# OMD_DRIVER_60V.net
KiCad netlist of a schematic drawn in Altium Designer
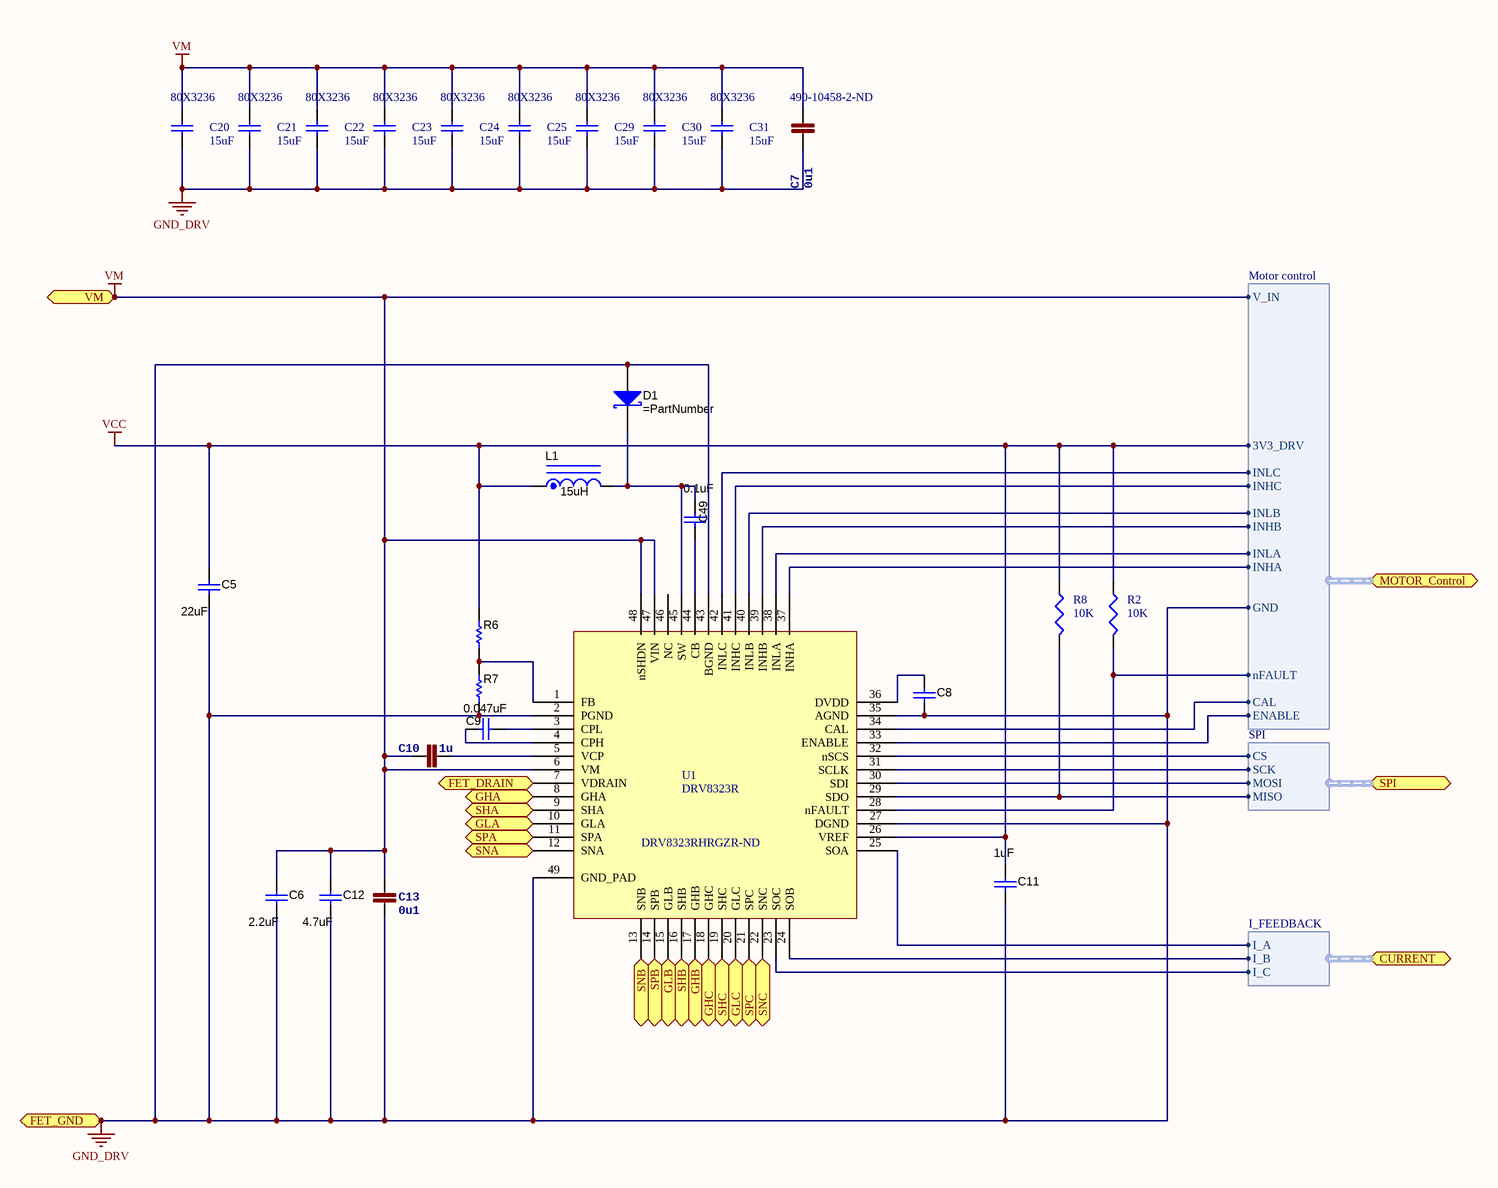
[diagram p0: OMD_DRIVER_60V.SchDoc]

(export (version "E")
  (design (tool "Eeschema 10.0.6"))
  (components
    (comp (ref "C5")
      (value "22uF")
      (footprint "1206_180L")
      (description "CAP, CERM, 22 µF, 10 V, +/- 20%, X7S, 1206")
      (libsource (lib "OMD") (part "C3216X7S1A226M160AC"))
    )
    (comp (ref "C6")
      (value "2.2uF")
      (footprint "1210L")
      (description "CAP, CERM, 2.2 µF, 100 V, +/- 10%, X7R, 1210")
      (libsource (lib "OMD") (part "HMK325B7225KN-T"))
    )
    (comp (ref "C7")
      (value "0u1")
      (footprint "0402-CAP")
      (description "CAP CER 0.1UF 16V Y5V 0402")
      (fields (field (name "SUPPLIER PART NUMBER 1") "490-10458-2-ND"))
      (libsource (lib "OMD") (part "CAP0402"))
    )
    (comp (ref "C8")
      (value "~")
      (footprint "0603-CAP")
      (description "CAP, CERM, 1 µF, 6.3 V, +/- 10%, X7R, 0603")
      (libsource (lib "OMD") (part "GRM188R70J105KA01D"))
    )
    (comp (ref "C9")
      (value "0.047uF")
      (footprint "0603-CAP")
      (description "CAP, CERM, 0.047 µF, 100 V, +/- 10%, X7S, 0603")
      (libsource (lib "OMD") (part "C1608X7S2A473K080AB"))
    )
    (comp (ref "C10")
      (value "1u")
      (footprint "0805-CAP")
      (description "CAP CER 1UF 16V Y5V 0603")
      (libsource (lib "OMD") (part "CAP0603"))
    )
    (comp (ref "C11")
      (value "1uF")
      (footprint "0603-CAP")
      (description "CAP, CERM, 1 µF, 6.3 V, +/- 10%, X7R, 0603")
      (libsource (lib "OMD") (part "GRM188R70J105KA01D"))
    )
    (comp (ref "C12")
      (value "4.7uF")
      (footprint "1210_270L")
      (description "CAP, CERM, 4.7 µF, 80 V, +/- 10%, X7R, 1210")
      (libsource (lib "OMD") (part "GRM32ER71K475KE14L"))
    )
    (comp (ref "C13")
      (value "0u1")
      (footprint "0402-CAP")
      (description "CAP CER 0.1UF 16V Y5V 0402")
      (libsource (lib "OMD") (part "CAP0402"))
    )
    (comp (ref "C20")
      (value "15uF")
      (footprint "CAPC5750L")
      (description "Capacitor")
      (fields (field (name "SUPPLIER PART NUMBER 1") "80X3236") (field (name "Comment") "Cap"))
      (libsource (lib "OMD") (part "Cap"))
    )
    (comp (ref "C21")
      (value "15uF")
      (footprint "CAPC5750L")
      (description "Capacitor")
      (fields (field (name "SUPPLIER PART NUMBER 1") "80X3236") (field (name "Comment") "Cap"))
      (libsource (lib "OMD") (part "Cap"))
    )
    (comp (ref "C22")
      (value "15uF")
      (footprint "CAPC5750L")
      (description "Capacitor")
      (fields (field (name "SUPPLIER PART NUMBER 1") "80X3236") (field (name "Comment") "Cap"))
      (libsource (lib "OMD") (part "Cap"))
    )
    (comp (ref "C23")
      (value "15uF")
      (footprint "CAPC5750L")
      (description "Capacitor")
      (fields (field (name "SUPPLIER PART NUMBER 1") "80X3236") (field (name "Comment") "Cap"))
      (libsource (lib "OMD") (part "Cap"))
    )
    (comp (ref "C24")
      (value "15uF")
      (footprint "CAPC5750L")
      (description "Capacitor")
      (fields (field (name "SUPPLIER PART NUMBER 1") "80X3236") (field (name "Comment") "Cap"))
      (libsource (lib "OMD") (part "Cap"))
    )
    (comp (ref "C25")
      (value "15uF")
      (footprint "CAPC5750L")
      (description "Capacitor")
      (fields (field (name "SUPPLIER PART NUMBER 1") "80X3236") (field (name "Comment") "Cap"))
      (libsource (lib "OMD") (part "Cap"))
    )
    (comp (ref "C29")
      (value "15uF")
      (footprint "CAPC5750L")
      (description "Capacitor")
      (fields (field (name "SUPPLIER PART NUMBER 1") "80X3236") (field (name "Comment") "Cap"))
      (libsource (lib "OMD") (part "Cap"))
    )
    (comp (ref "C30")
      (value "15uF")
      (footprint "CAPC5750L")
      (description "Capacitor")
      (fields (field (name "SUPPLIER PART NUMBER 1") "80X3236") (field (name "Comment") "Cap"))
      (libsource (lib "OMD") (part "Cap"))
    )
    (comp (ref "C31")
      (value "15uF")
      (footprint "CAPC5750L")
      (description "Capacitor")
      (fields (field (name "SUPPLIER PART NUMBER 1") "80X3236") (field (name "Comment") "Cap"))
      (libsource (lib "OMD") (part "Cap"))
    )
    (comp (ref "C49")
      (value "0.1uF")
      (footprint "0603-CAP")
      (description "CAP, CERM, 0.1 µF, 16 V, +/- 5%, X7R, 0603")
      (libsource (lib "OMD") (part "0603YC104JAT2A"))
    )
    (comp (ref "D1")
      (value "~")
      (footprint "SOD-123FL")
      (description "Diode, Schottky, 100 V, 1 A, SOD-123FL")
      (libsource (lib "OMD") (part "MBR1H100SFT3G"))
    )
    (comp (ref "L1")
      (value "15uH")
      (footprint "SD53")
      (description "Inductor, Shielded Drum Core, Ferrite, 15 µH, 1.1 A, 0.122 ohm, SMD")
      (libsource (lib "OMD") (part "SD53-150-R"))
    )
    (comp (ref "R2")
      (value "10K")
      (footprint "0402-RES")
      (description "RES SMD 10K OHM 5% 1/16W 0402")
      (libsource (lib "OMD") (part "Resistor"))
    )
    (comp (ref "R6")
      (value "~")
      (footprint "0603L")
      (description "RES, 28.0 k, 1%, 0.1 W, 0603")
      (libsource (lib "OMD") (part "CRCW060328K0FKEA"))
    )
    (comp (ref "R7")
      (value "~")
      (footprint "0603L")
      (description "RES, 8.45 k, 1%, 0.1 W, 0603")
      (libsource (lib "OMD") (part "CRCW06038K45FKEA"))
    )
    (comp (ref "R8")
      (value "10K")
      (footprint "0402-RES")
      (description "RES SMD 10K OHM 5% 1/16W 0402")
      (libsource (lib "OMD") (part "Resistor"))
    )
    (comp (ref "U1")
      (value "DRV8323R")
      (footprint "PQFP-G48")
      (fields (field (name "SUPPLIER PART NUMBER 1") "DRV8323RHRGZR-ND"))
      (libsource (lib "OMD") (part "DRV8323R"))
    )
  )
  (nets
    (net (code "5") (name "/CAL") (class "Default")
      (node (ref "U1") (pin "34") (pinfunction "CAL_34") (pintype "passive"))
    )
    (net (code "6") (name "/CS") (class "Default")
      (node (ref "U1") (pin "32") (pinfunction "nSCS_32") (pintype "passive"))
    )
    (net (code "7") (name "/ENABLE") (class "Default")
      (node (ref "U1") (pin "33") (pinfunction "ENABLE_33") (pintype "passive"))
    )
    (net (code "8") (name "/FET_DRAIN") (class "Default")
      (node (ref "U1") (pin "7") (pinfunction "VDRAIN_7") (pintype "passive"))
    )
    (net (code "9") (name "/GHA") (class "Default")
      (node (ref "U1") (pin "8") (pinfunction "GHA_8") (pintype "passive"))
    )
    (net (code "10") (name "/GHB") (class "Default")
      (node (ref "U1") (pin "17") (pinfunction "GHB_17") (pintype "passive"))
    )
    (net (code "11") (name "/GHC") (class "Default")
      (node (ref "U1") (pin "18") (pinfunction "GHC_18") (pintype "passive"))
    )
    (net (code "12") (name "/GLA") (class "Default")
      (node (ref "U1") (pin "10") (pinfunction "GLA_10") (pintype "passive"))
    )
    (net (code "13") (name "/GLB") (class "Default")
      (node (ref "U1") (pin "15") (pinfunction "GLB_15") (pintype "passive"))
    )
    (net (code "14") (name "/GLC") (class "Default")
      (node (ref "U1") (pin "20") (pinfunction "GLC_20") (pintype "passive"))
    )
    (net (code "15") (name "/INHA") (class "Default")
      (node (ref "U1") (pin "37") (pinfunction "INHA_37") (pintype "passive"))
    )
    (net (code "16") (name "/INHB") (class "Default")
      (node (ref "U1") (pin "39") (pinfunction "INHB_39") (pintype "passive"))
    )
    (net (code "17") (name "/INHC") (class "Default")
      (node (ref "U1") (pin "41") (pinfunction "INHC_41") (pintype "passive"))
    )
    (net (code "18") (name "/INLA") (class "Default")
      (node (ref "U1") (pin "38") (pinfunction "INLA_38") (pintype "passive"))
    )
    (net (code "19") (name "/INLB") (class "Default")
      (node (ref "U1") (pin "40") (pinfunction "INLB_40") (pintype "passive"))
    )
    (net (code "20") (name "/INLC") (class "Default")
      (node (ref "U1") (pin "42") (pinfunction "INLC_42") (pintype "passive"))
    )
    (net (code "21") (name "/I_A") (class "Default")
      (node (ref "U1") (pin "25") (pinfunction "SOA_25") (pintype "passive"))
    )
    (net (code "22") (name "/I_B") (class "Default")
      (node (ref "U1") (pin "24") (pinfunction "SOB_24") (pintype "passive"))
    )
    (net (code "23") (name "/I_C") (class "Default")
      (node (ref "U1") (pin "23") (pinfunction "SOC_23") (pintype "passive"))
    )
    (net (code "24") (name "/MISO") (class "Default")
      (node (ref "R8") (pin "2") (pinfunction "2_2") (pintype "passive"))
      (node (ref "U1") (pin "29") (pinfunction "SDO_29") (pintype "passive"))
    )
    (net (code "25") (name "/MOSI") (class "Default")
      (node (ref "U1") (pin "30") (pinfunction "SDI_30") (pintype "passive"))
    )
    (net (code "26") (name "/SCK") (class "Default")
      (node (ref "U1") (pin "31") (pinfunction "SCLK_31") (pintype "passive"))
    )
    (net (code "27") (name "/SHA") (class "Default")
      (node (ref "U1") (pin "9") (pinfunction "SHA_9") (pintype "passive"))
    )
    (net (code "28") (name "/SHB") (class "Default")
      (node (ref "U1") (pin "16") (pinfunction "SHB_16") (pintype "passive"))
    )
    (net (code "29") (name "/SHC") (class "Default")
      (node (ref "U1") (pin "19") (pinfunction "SHC_19") (pintype "passive"))
    )
    (net (code "30") (name "/SNA") (class "Default")
      (node (ref "U1") (pin "12") (pinfunction "SNA_12") (pintype "passive"))
    )
    (net (code "31") (name "/SNB") (class "Default")
      (node (ref "U1") (pin "13") (pinfunction "SNB_13") (pintype "passive"))
    )
    (net (code "32") (name "/SNC") (class "Default")
      (node (ref "U1") (pin "22") (pinfunction "SNC_22") (pintype "passive"))
    )
    (net (code "33") (name "/SPA") (class "Default")
      (node (ref "U1") (pin "11") (pinfunction "SPA_11") (pintype "passive"))
    )
    (net (code "34") (name "/SPB") (class "Default")
      (node (ref "U1") (pin "14") (pinfunction "SPB_14") (pintype "passive"))
    )
    (net (code "35") (name "/SPC") (class "Default")
      (node (ref "U1") (pin "21") (pinfunction "SPC_21") (pintype "passive"))
    )
    (net (code "36") (name "/nFAULT") (class "Default")
      (node (ref "R2") (pin "2") (pinfunction "2_2") (pintype "passive"))
      (node (ref "U1") (pin "28") (pinfunction "nFAULT_28") (pintype "passive"))
    )
    (net (code "40") (name "GND_DRV") (class "Default")
      (node (ref "C11") (pin "1") (pinfunction "1_1") (pintype "passive"))
      (node (ref "C12") (pin "2") (pinfunction "2_2") (pintype "passive"))
      (node (ref "C13") (pin "P$2") (pinfunction "2_P$2") (pintype "passive"))
      (node (ref "C20") (pin "1") (pinfunction "1_1") (pintype "passive"))
      (node (ref "C21") (pin "1") (pinfunction "1_1") (pintype "passive"))
      (node (ref "C22") (pin "1") (pinfunction "1_1") (pintype "passive"))
      (node (ref "C23") (pin "1") (pinfunction "1_1") (pintype "passive"))
      (node (ref "C24") (pin "1") (pinfunction "1_1") (pintype "passive"))
      (node (ref "C25") (pin "1") (pinfunction "1_1") (pintype "passive"))
      (node (ref "C29") (pin "1") (pinfunction "1_1") (pintype "passive"))
      (node (ref "C30") (pin "1") (pinfunction "1_1") (pintype "passive"))
      (node (ref "C31") (pin "1") (pinfunction "1_1") (pintype "passive"))
      (node (ref "C5") (pin "2") (pinfunction "2_2") (pintype "passive"))
      (node (ref "C6") (pin "2") (pinfunction "2_2") (pintype "passive"))
      (node (ref "C7") (pin "P$2") (pinfunction "2_P$2") (pintype "passive"))
      (node (ref "C8") (pin "2") (pinfunction "2_2") (pintype "passive"))
      (node (ref "D1") (pin "2") (pinfunction "A_2") (pintype "passive"))
      (node (ref "R7") (pin "1") (pinfunction "1_1") (pintype "passive"))
      (node (ref "U1") (pin "2") (pinfunction "PGND_2") (pintype "passive"))
      (node (ref "U1") (pin "27") (pinfunction "DGND_27") (pintype "passive"))
      (node (ref "U1") (pin "35") (pinfunction "AGND_35") (pintype "passive"))
      (node (ref "U1") (pin "43") (pinfunction "BGND_43") (pintype "passive"))
      (node (ref "U1") (pin "49") (pinfunction "GND_PAD_49") (pintype "passive"))
    )
    (net (code "41") (name "Net-(D1-K)") (class "Default")
      (node (ref "C49") (pin "1") (pinfunction "1_1") (pintype "passive"))
      (node (ref "D1") (pin "1") (pinfunction "K_1") (pintype "passive"))
      (node (ref "L1") (pin "2") (pinfunction "2_2") (pintype "passive"))
      (node (ref "U1") (pin "45") (pinfunction "SW_45") (pintype "passive"))
    )
    (net (code "42") (name "Net-(U1-CB)") (class "Default")
      (node (ref "C49") (pin "2") (pinfunction "2_2") (pintype "passive"))
      (node (ref "U1") (pin "44") (pinfunction "CB_44") (pintype "passive"))
    )
    (net (code "43") (name "Net-(U1-CPH)") (class "Default")
      (node (ref "C9") (pin "2") (pinfunction "2_2") (pintype "passive"))
      (node (ref "U1") (pin "4") (pinfunction "CPH_4") (pintype "passive"))
    )
    (net (code "44") (name "Net-(U1-CPL)") (class "Default")
      (node (ref "C9") (pin "1") (pinfunction "1_1") (pintype "passive"))
      (node (ref "U1") (pin "3") (pinfunction "CPL_3") (pintype "passive"))
    )
    (net (code "45") (name "Net-(U1-DVDD)") (class "Default")
      (node (ref "C8") (pin "1") (pinfunction "1_1") (pintype "passive"))
      (node (ref "U1") (pin "36") (pinfunction "DVDD_36") (pintype "passive"))
    )
    (net (code "46") (name "Net-(U1-FB)") (class "Default")
      (node (ref "R6") (pin "1") (pinfunction "1_1") (pintype "passive"))
      (node (ref "R7") (pin "2") (pinfunction "2_2") (pintype "passive"))
      (node (ref "U1") (pin "1") (pinfunction "FB_1") (pintype "passive"))
    )
    (net (code "47") (name "Net-(U1-VCP)") (class "Default")
      (node (ref "C10") (pin "1") (pinfunction "1_1") (pintype "passive"))
      (node (ref "U1") (pin "5") (pinfunction "VCP_5") (pintype "passive"))
    )
    (net (code "48") (name "VCC") (class "Default")
      (node (ref "C11") (pin "2") (pinfunction "2_2") (pintype "passive"))
      (node (ref "C5") (pin "1") (pinfunction "1_1") (pintype "passive"))
      (node (ref "L1") (pin "1") (pinfunction "1_1") (pintype "passive"))
      (node (ref "R2") (pin "1") (pinfunction "1_1") (pintype "passive"))
      (node (ref "R6") (pin "2") (pinfunction "2_2") (pintype "passive"))
      (node (ref "R8") (pin "1") (pinfunction "1_1") (pintype "passive"))
      (node (ref "U1") (pin "26") (pinfunction "VREF_26") (pintype "passive"))
    )
    (net (code "49") (name "VM") (class "Default")
      (node (ref "C10") (pin "2") (pinfunction "2_2") (pintype "passive"))
      (node (ref "C12") (pin "1") (pinfunction "1_1") (pintype "passive"))
      (node (ref "C13") (pin "P$1") (pinfunction "1_P$1") (pintype "passive"))
      (node (ref "C20") (pin "2") (pinfunction "2_2") (pintype "passive"))
      (node (ref "C21") (pin "2") (pinfunction "2_2") (pintype "passive"))
      (node (ref "C22") (pin "2") (pinfunction "2_2") (pintype "passive"))
      (node (ref "C23") (pin "2") (pinfunction "2_2") (pintype "passive"))
      (node (ref "C24") (pin "2") (pinfunction "2_2") (pintype "passive"))
      (node (ref "C25") (pin "2") (pinfunction "2_2") (pintype "passive"))
      (node (ref "C29") (pin "2") (pinfunction "2_2") (pintype "passive"))
      (node (ref "C30") (pin "2") (pinfunction "2_2") (pintype "passive"))
      (node (ref "C31") (pin "2") (pinfunction "2_2") (pintype "passive"))
      (node (ref "C6") (pin "1") (pinfunction "1_1") (pintype "passive"))
      (node (ref "C7") (pin "P$1") (pinfunction "1_P$1") (pintype "passive"))
      (node (ref "U1") (pin "47") (pinfunction "VIN_47") (pintype "passive"))
      (node (ref "U1") (pin "48") (pinfunction "nSHDN_48") (pintype "passive"))
      (node (ref "U1") (pin "6") (pinfunction "VM_6") (pintype "passive"))
    )
    (net (code "50") (name "unconnected-(U1-NC-Pad46)") (class "Default")
      (node (ref "U1") (pin "46") (pinfunction "NC_46") (pintype "passive"))
    )
  )
)
